# Pinguino-PIC18F2550-ICSP-Pk3.net
KiCad netlist of a schematic drawn in EAGLE
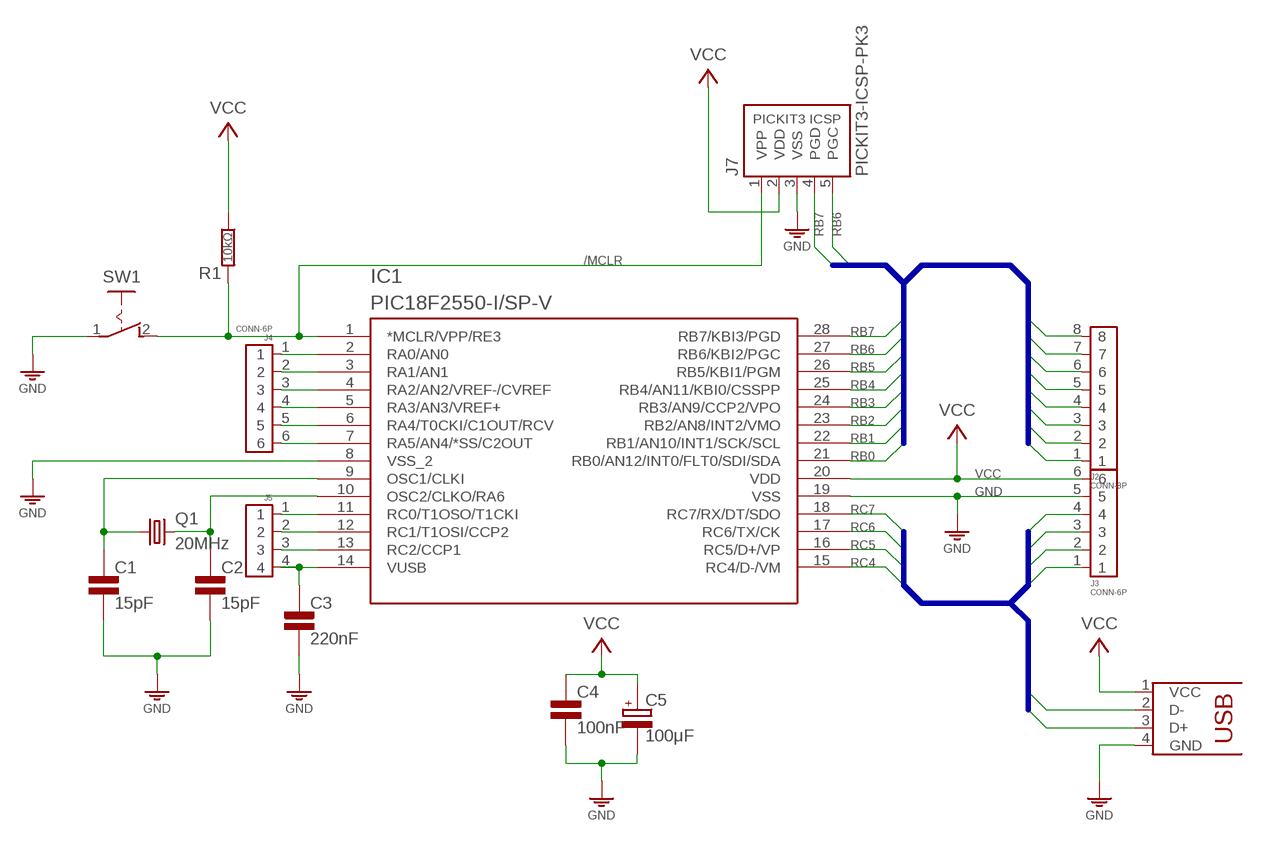
[diagram p0: schematic, sheet 1]

(export (version "E")
  (design (tool "Eeschema 10.0.6"))
  (components
    (comp (ref "C1")
      (value "15pF")
      (footprint "eagle-import:C025-015X024")
      (libsource (lib "eagle-import") (part "C025-015X024"))
    )
    (comp (ref "C2")
      (value "15pF")
      (footprint "eagle-import:C025-015X024")
      (libsource (lib "eagle-import") (part "C025-015X024"))
    )
    (comp (ref "C3")
      (value "220nF")
      (footprint "eagle-import:C075-032X103")
      (libsource (lib "eagle-import") (part "C075-032X103"))
    )
    (comp (ref "C4")
      (value "100nF")
      (footprint "eagle-import:C025-015X024")
      (libsource (lib "eagle-import") (part "C025-015X024"))
    )
    (comp (ref "C5")
      (value "100μF")
      (footprint "eagle-import:E2,5-4")
      (libsource (lib "eagle-import") (part "CPOLE2,5-4"))
    )
    (comp (ref "IC1")
      (value "PIC18F2550-I/SP-V")
      (footprint "eagle-import:DIL28-3_V")
      (libsource (lib "eagle-import") (part "PIC18F2550-I/SP-V"))
    )
    (comp (ref "J1")
      (value "USB-PRINT")
      (footprint "eagle-import:USB-B-PRINT")
      (libsource (lib "eagle-import") (part "USB-PRINT"))
    )
    (comp (ref "J2")
      (value "CONN-8P")
      (footprint "eagle-import:CONN-8P")
      (libsource (lib "eagle-import") (part "CONN-8P"))
    )
    (comp (ref "J3")
      (value "CONN-6P")
      (footprint "eagle-import:CONN-6P")
      (libsource (lib "eagle-import") (part "CONN-6P"))
    )
    (comp (ref "J4")
      (value "CONN-6P")
      (footprint "eagle-import:CONN-6P")
      (libsource (lib "eagle-import") (part "CONN-6P"))
    )
    (comp (ref "J5")
      (value "CONN-4P-4P")
      (footprint "eagle-import:CONN-4P")
      (libsource (lib "eagle-import") (part "CONN-4P-4P"))
    )
    (comp (ref "J7")
      (value "PICKIT3-ICSP-PK3")
      (footprint "eagle-import:PIC-PK3")
      (libsource (lib "eagle-import") (part "PICKIT3-ICSP-PK3"))
    )
    (comp (ref "J8")
      (value "VCC_GNDPWR-R")
      (footprint "eagle-import:PWR-R")
      (libsource (lib "eagle-import") (part "VCC_GNDPWR-R"))
    )
    (comp (ref "Q1")
      (value "20MHz")
      (footprint "eagle-import:HC49")
      (libsource (lib "eagle-import") (part "CRYSTALHC49"))
    )
    (comp (ref "R1")
      (value "10kΩ")
      (footprint "eagle-import:0204_10")
      (libsource (lib "eagle-import") (part "R0204/10"))
    )
    (comp (ref "SW1")
      (value "PB-1P-1T")
      (footprint "eagle-import:PB-1P1T")
      (libsource (lib "eagle-import") (part "PB-1P-1T"))
    )
  )
  (nets
    (net (code "1") (name "/RB0") (class "Default")
      (node (ref "IC1") (pin "21") (pinfunction "RB0/AN12/INT0/FLT0/SDI/SDA_21") (pintype "passive"))
      (node (ref "J2") (pin "1") (pinfunction "1_1") (pintype "passive"))
    )
    (net (code "2") (name "/RB1") (class "Default")
      (node (ref "IC1") (pin "22") (pinfunction "RB1/AN10/INT1/SCK/SCL_22") (pintype "passive"))
      (node (ref "J2") (pin "2") (pinfunction "2_2") (pintype "passive"))
    )
    (net (code "3") (name "/RB2") (class "Default")
      (node (ref "IC1") (pin "23") (pinfunction "RB2/AN8/INT2/VMO_23") (pintype "passive"))
      (node (ref "J2") (pin "3") (pinfunction "3_3") (pintype "passive"))
    )
    (net (code "4") (name "/RB3") (class "Default")
      (node (ref "IC1") (pin "24") (pinfunction "RB3/AN9/CCP2/VPO_24") (pintype "passive"))
      (node (ref "J2") (pin "4") (pinfunction "4_4") (pintype "passive"))
    )
    (net (code "5") (name "/RB4") (class "Default")
      (node (ref "IC1") (pin "25") (pinfunction "RB4/AN11/KBI0/CSSPP_25") (pintype "passive"))
      (node (ref "J2") (pin "5") (pinfunction "5_5") (pintype "passive"))
    )
    (net (code "6") (name "/RB5") (class "Default")
      (node (ref "IC1") (pin "26") (pinfunction "RB5/KBI1/PGM_26") (pintype "passive"))
      (node (ref "J2") (pin "6") (pinfunction "6_6") (pintype "passive"))
    )
    (net (code "7") (name "/RB6") (class "Default")
      (node (ref "IC1") (pin "27") (pinfunction "RB6/KBI2/PGC_27") (pintype "passive"))
      (node (ref "J2") (pin "7") (pinfunction "7_7") (pintype "passive"))
      (node (ref "J7") (pin "5") (pinfunction "PGC_5") (pintype "passive"))
    )
    (net (code "8") (name "/RB7") (class "Default")
      (node (ref "IC1") (pin "28") (pinfunction "RB7/KBI3/PGD_28") (pintype "passive"))
      (node (ref "J2") (pin "8") (pinfunction "8_8") (pintype "passive"))
      (node (ref "J7") (pin "4") (pinfunction "PGD_4") (pintype "passive"))
    )
    (net (code "9") (name "/RC4") (class "Default")
      (node (ref "IC1") (pin "15") (pinfunction "RC4/D-/VM_15") (pintype "passive"))
      (node (ref "J1") (pin "3") (pinfunction "D+_3") (pintype "bidirectional"))
      (node (ref "J3") (pin "1") (pinfunction "1_1") (pintype "passive"))
    )
    (net (code "10") (name "/RC5") (class "Default")
      (node (ref "IC1") (pin "16") (pinfunction "RC5/D+/VP_16") (pintype "passive"))
      (node (ref "J1") (pin "2") (pinfunction "D-_2") (pintype "bidirectional"))
      (node (ref "J3") (pin "2") (pinfunction "2_2") (pintype "passive"))
    )
    (net (code "11") (name "/RC6") (class "Default")
      (node (ref "IC1") (pin "17") (pinfunction "RC6/TX/CK_17") (pintype "passive"))
      (node (ref "J3") (pin "3") (pinfunction "3_3") (pintype "passive"))
    )
    (net (code "12") (name "/RC7") (class "Default")
      (node (ref "IC1") (pin "18") (pinfunction "RC7/RX/DT/SDO_18") (pintype "passive"))
      (node (ref "J3") (pin "4") (pinfunction "4_4") (pintype "passive"))
    )
    (net (code "13") (name "/{slash}MCLR") (class "Default")
      (node (ref "IC1") (pin "1") (pinfunction "*MCLR/VPP/RE3_1") (pintype "passive"))
      (node (ref "J7") (pin "1") (pinfunction "VPP_1") (pintype "passive"))
      (node (ref "R1") (pin "2") (pinfunction "2_2") (pintype "passive"))
      (node (ref "SW1") (pin "2") (pinfunction "S_2") (pintype "passive"))
    )
    (net (code "14") (name "GND") (class "Default")
      (node (ref "C1") (pin "2") (pinfunction "2_2") (pintype "passive"))
      (node (ref "C2") (pin "2") (pinfunction "2_2") (pintype "passive"))
      (node (ref "C3") (pin "2") (pinfunction "2_2") (pintype "passive"))
      (node (ref "C4") (pin "2") (pinfunction "2_2") (pintype "passive"))
      (node (ref "C5") (pin "-") (pinfunction "-_-") (pintype "passive"))
      (node (ref "IC1") (pin "19") (pinfunction "VSS_19") (pintype "passive"))
      (node (ref "IC1") (pin "8") (pinfunction "VSS_2_8") (pintype "passive"))
      (node (ref "J1") (pin "4") (pinfunction "GND_4") (pintype "bidirectional"))
      (node (ref "J3") (pin "5") (pinfunction "5_5") (pintype "passive"))
      (node (ref "J7") (pin "3") (pinfunction "VSS_3") (pintype "passive"))
      (node (ref "J8") (pin "1") (pinfunction "GND_1") (pintype "power_in"))
      (node (ref "SW1") (pin "1") (pinfunction "P_1") (pintype "passive"))
    )
    (net (code "15") (name "Net-(IC1-OSC1{slash}CLKI)") (class "Default")
      (node (ref "C1") (pin "1") (pinfunction "1_1") (pintype "passive"))
      (node (ref "IC1") (pin "9") (pinfunction "OSC1/CLKI_9") (pintype "passive"))
      (node (ref "Q1") (pin "1") (pinfunction "1_1") (pintype "passive"))
    )
    (net (code "16") (name "Net-(IC1-OSC2{slash}CLKO{slash}RA6)") (class "Default")
      (node (ref "C2") (pin "1") (pinfunction "1_1") (pintype "passive"))
      (node (ref "IC1") (pin "10") (pinfunction "OSC2/CLKO/RA6_10") (pintype "passive"))
      (node (ref "Q1") (pin "2") (pinfunction "2_2") (pintype "passive"))
    )
    (net (code "17") (name "Net-(IC1-RA0{slash}AN0)") (class "Default")
      (node (ref "IC1") (pin "2") (pinfunction "RA0/AN0_2") (pintype "passive"))
      (node (ref "J4") (pin "1") (pinfunction "1_1") (pintype "passive"))
    )
    (net (code "18") (name "Net-(IC1-RA1{slash}AN1)") (class "Default")
      (node (ref "IC1") (pin "3") (pinfunction "RA1/AN1_3") (pintype "passive"))
      (node (ref "J4") (pin "2") (pinfunction "2_2") (pintype "passive"))
    )
    (net (code "19") (name "Net-(IC1-RA2{slash}AN2{slash}VREF-{slash}CVREF)") (class "Default")
      (node (ref "IC1") (pin "4") (pinfunction "RA2/AN2/VREF-/CVREF_4") (pintype "passive"))
      (node (ref "J4") (pin "3") (pinfunction "3_3") (pintype "passive"))
    )
    (net (code "20") (name "Net-(IC1-RA3{slash}AN3{slash}VREF+)") (class "Default")
      (node (ref "IC1") (pin "5") (pinfunction "RA3/AN3/VREF+_5") (pintype "passive"))
      (node (ref "J4") (pin "4") (pinfunction "4_4") (pintype "passive"))
    )
    (net (code "21") (name "Net-(IC1-RA4{slash}T0CKI{slash}C1OUT{slash}RCV)") (class "Default")
      (node (ref "IC1") (pin "6") (pinfunction "RA4/T0CKI/C1OUT/RCV_6") (pintype "passive"))
      (node (ref "J4") (pin "5") (pinfunction "5_5") (pintype "passive"))
    )
    (net (code "22") (name "Net-(IC1-RA5{slash}AN4{slash}*SS{slash}C2OUT)") (class "Default")
      (node (ref "IC1") (pin "7") (pinfunction "RA5/AN4/*SS/C2OUT_7") (pintype "passive"))
      (node (ref "J4") (pin "6") (pinfunction "6_6") (pintype "passive"))
    )
    (net (code "23") (name "Net-(IC1-RC0{slash}T1OSO{slash}T1CKI)") (class "Default")
      (node (ref "IC1") (pin "11") (pinfunction "RC0/T1OSO/T1CKI_11") (pintype "passive"))
      (node (ref "J5") (pin "1") (pinfunction "1_1") (pintype "bidirectional"))
    )
    (net (code "24") (name "Net-(IC1-RC1{slash}T1OSI{slash}CCP2)") (class "Default")
      (node (ref "IC1") (pin "12") (pinfunction "RC1/T1OSI/CCP2_12") (pintype "passive"))
      (node (ref "J5") (pin "2") (pinfunction "2_2") (pintype "bidirectional"))
    )
    (net (code "25") (name "Net-(IC1-RC2{slash}CCP1)") (class "Default")
      (node (ref "IC1") (pin "13") (pinfunction "RC2/CCP1_13") (pintype "passive"))
      (node (ref "J5") (pin "3") (pinfunction "3_3") (pintype "bidirectional"))
    )
    (net (code "26") (name "Net-(IC1-VUSB)") (class "Default")
      (node (ref "C3") (pin "1") (pinfunction "1_1") (pintype "passive"))
      (node (ref "IC1") (pin "14") (pinfunction "VUSB_14") (pintype "passive"))
      (node (ref "J5") (pin "4") (pinfunction "4_4") (pintype "bidirectional"))
    )
    (net (code "27") (name "VCC") (class "Default")
      (node (ref "C4") (pin "1") (pinfunction "1_1") (pintype "passive"))
      (node (ref "C5") (pin "+") (pinfunction "+_+") (pintype "passive"))
      (node (ref "IC1") (pin "20") (pinfunction "VDD_20") (pintype "passive"))
      (node (ref "J1") (pin "1") (pinfunction "VCC_1") (pintype "bidirectional"))
      (node (ref "J3") (pin "6") (pinfunction "6_6") (pintype "passive"))
      (node (ref "J7") (pin "2") (pinfunction "VDD_2") (pintype "passive"))
      (node (ref "J8") (pin "2") (pinfunction "VCC_2") (pintype "power_in"))
      (node (ref "R1") (pin "1") (pinfunction "1_1") (pintype "passive"))
    )
  )
)
